# SPI_Stuff.net
KiCad netlist of a schematic drawn in Altium Designer
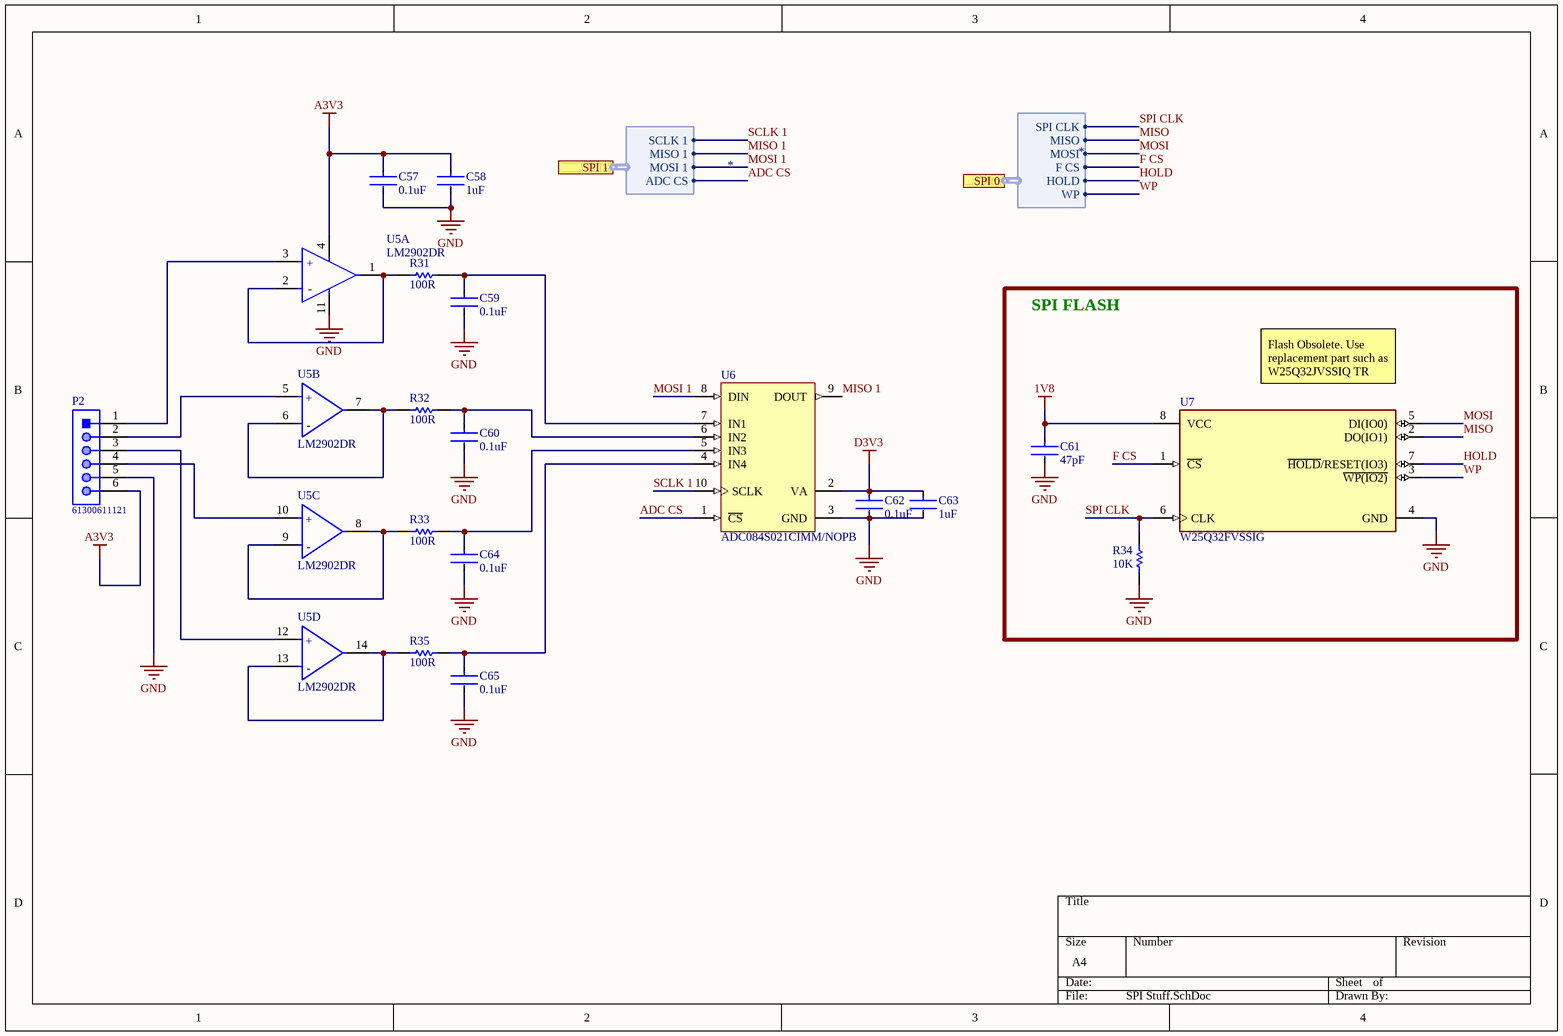
[diagram p0: SPI Stuff.SchDoc]

(export (version "E")
  (design (tool "Eeschema 10.0.6"))
  (components
    (comp (ref "C57")
      (value "0.1uF")
      (footprint "FP-GRM15-MFG")
      (description "CAP CER 0.1UF 16V X7R 0402")
      (fields (field (name "MANUFACTURER PART NUMBER") "GRM155R71C104KA88D") (field (name "TOLERANCE") "10%"))
      (libsource (lib "Altium Content Vault") (part "236180d848d6139a670b325ea6854c9"))
    )
    (comp (ref "C58")
      (value "1uF")
      (footprint "FP-GRM15-MFG")
      (description "CAP CER 0.1UF 16V X7R 0402")
      (fields (field (name "MANUFACTURER PART NUMBER") "GRM155R71C104KA88D") (field (name "TOLERANCE") "10%"))
      (libsource (lib "Altium Content Vault") (part "236180d848d6139a670b325ea6854c9"))
    )
    (comp (ref "C59")
      (value "0.1uF")
      (footprint "FP-GRM15-MFG")
      (description "CAP CER 0.1UF 16V X7R 0402")
      (fields (field (name "MANUFACTURER PART NUMBER") "GRM155R71C104KA88D") (field (name "TOLERANCE") "10%"))
      (libsource (lib "Altium Content Vault") (part "236180d848d6139a670b325ea6854c9"))
    )
    (comp (ref "C60")
      (value "0.1uF")
      (footprint "FP-GRM15-MFG")
      (description "CAP CER 0.1UF 16V X7R 0402")
      (fields (field (name "MANUFACTURER PART NUMBER") "GRM155R71C104KA88D") (field (name "TOLERANCE") "10%"))
      (libsource (lib "Altium Content Vault") (part "236180d848d6139a670b325ea6854c9"))
    )
    (comp (ref "C61")
      (value "47pF")
      (footprint "FP-GRM15-MFG")
      (description "CAP CER 0.1UF 16V X7R 0402")
      (fields (field (name "MANUFACTURER PART NUMBER") "GRM155R71C104KA88D") (field (name "TOLERANCE") "10%"))
      (libsource (lib "Altium Content Vault") (part "236180d848d6139a670b325ea6854c9"))
    )
    (comp (ref "C62")
      (value "0.1uF")
      (footprint "FP-GRM15-MFG")
      (description "CAP CER 0.1UF 16V X7R 0402")
      (fields (field (name "MANUFACTURER PART NUMBER") "GRM155R71C104KA88D") (field (name "TOLERANCE") "10%"))
      (libsource (lib "Altium Content Vault") (part "236180d848d6139a670b325ea6854c9"))
    )
    (comp (ref "C63")
      (value "1uF")
      (footprint "FP-GRM15-MFG")
      (description "CAP CER 0.1UF 16V X7R 0402")
      (fields (field (name "MANUFACTURER PART NUMBER") "GRM155R71C104KA88D") (field (name "TOLERANCE") "10%"))
      (libsource (lib "Altium Content Vault") (part "236180d848d6139a670b325ea6854c9"))
    )
    (comp (ref "C64")
      (value "0.1uF")
      (footprint "FP-GRM15-MFG")
      (description "CAP CER 0.1UF 16V X7R 0402")
      (fields (field (name "MANUFACTURER PART NUMBER") "GRM155R71C104KA88D") (field (name "TOLERANCE") "10%"))
      (libsource (lib "Altium Content Vault") (part "236180d848d6139a670b325ea6854c9"))
    )
    (comp (ref "C65")
      (value "0.1uF")
      (footprint "FP-GRM15-MFG")
      (description "CAP CER 0.1UF 16V X7R 0402")
      (fields (field (name "MANUFACTURER PART NUMBER") "GRM155R71C104KA88D") (field (name "TOLERANCE") "10%"))
      (libsource (lib "Altium Content Vault") (part "236180d848d6139a670b325ea6854c9"))
    )
    (comp (ref "P2")
      (value "61300611121")
      (footprint "61300611121")
      (description "THT Vertical Pin Header WR-PHD, Pitch 2.54 mm, Single Row, 6 pins")
      (fields (field (name "MANUFACTURER") "Wurth Elektronik") (field (name "PUBLISHER") "WurthElektronik"))
      (libsource (lib "Altium Content Vault") (part "WE-CN-1P-M-R6"))
    )
    (comp (ref "R31")
      (value "100R")
      (footprint "RESC1005X40X25LL05T05")
      (description "Chip Resistor, 0 Ohm, 0.1 W, -55 to 155 degC, 0402 (1005 Metric), RoHS, Tape and Reel")
      (fields (field (name "MANUFACTURER") "Panasonic") (field (name "TOLERANCE") "5%"))
      (libsource (lib "Altium Content Vault") (part "RES-2"))
    )
    (comp (ref "R32")
      (value "100R")
      (footprint "RESC1005X40X25LL05T05")
      (description "Chip Resistor, 0 Ohm, 0.1 W, -55 to 155 degC, 0402 (1005 Metric), RoHS, Tape and Reel")
      (fields (field (name "MANUFACTURER") "Panasonic") (field (name "TOLERANCE") "5%"))
      (libsource (lib "Altium Content Vault") (part "RES-2"))
    )
    (comp (ref "R33")
      (value "100R")
      (footprint "RESC1005X40X25LL05T05")
      (description "Chip Resistor, 0 Ohm, 0.1 W, -55 to 155 degC, 0402 (1005 Metric), RoHS, Tape and Reel")
      (fields (field (name "MANUFACTURER") "Panasonic") (field (name "TOLERANCE") "5%"))
      (libsource (lib "Altium Content Vault") (part "RES-2"))
    )
    (comp (ref "R34")
      (value "10K")
      (footprint "RESC1005X40X25LL05T05")
      (description "Chip Resistor, 0 Ohm, 0.1 W, -55 to 155 degC, 0402 (1005 Metric), RoHS, Tape and Reel")
      (fields (field (name "MANUFACTURER") "Panasonic") (field (name "TOLERANCE") "5%"))
      (libsource (lib "Altium Content Vault") (part "RES-2"))
    )
    (comp (ref "R35")
      (value "100R")
      (footprint "RESC1005X40X25LL05T05")
      (description "Chip Resistor, 0 Ohm, 0.1 W, -55 to 155 degC, 0402 (1005 Metric), RoHS, Tape and Reel")
      (fields (field (name "MANUFACTURER") "Panasonic") (field (name "TOLERANCE") "5%"))
      (libsource (lib "Altium Content Vault") (part "RES-2"))
    )
    (comp (ref "U5")
      (value "LM2902DR")
      (footprint "FP-D0014A-IPC_A")
      (description "IC OPAMP GP 4 CIRCUIT 14SOIC")
      (libsource (lib "Altium Content Vault") (part "b02d0cb41c0d90ddc6f34c0e90b5c12"))
    )
    (comp (ref "U6")
      (value "ADC084S021CIMM/NOPB")
      (footprint "MUB10A_N")
      (description "4 Channel, 50 kSPS to 200 kSPS, 8-Bit A/D Converter, 10-pin Mini SOIC, Pb-Free")
      (fields (field (name "MANUFACTURER") "National Semiconductor"))
      (libsource (lib "Altium Content Vault") (part "CON-ADC-ADC104S101CIMM"))
    )
    (comp (ref "U7")
      (value "W25Q32FVSSIG")
      (footprint "FP-SS-MFG")
      (description "IC FLASH 32M SPI 104MHZ 8SOIC")
      (fields
        (field (name "MANUFACTURER") "Winbond")
        (field (name "OCTOPART") "https://octopart.com/w25q32fvssig-winbond-23896462")
      )
      (libsource (lib "Altium Content Vault") (part "4804fbe011262506d6ec6a9051036b0"))
    )
  )
  (nets
    (net (code "2") (name "/ADC CS") (class "Default")
      (node (ref "U6") (pin "1") (pinfunction "~{CS}_1") (pintype "input"))
    )
    (net (code "3") (name "/F CS") (class "Default")
      (node (ref "U7") (pin "1") (pinfunction "~{CS}_1") (pintype "input"))
    )
    (net (code "4") (name "/HOLD") (class "Default")
      (node (ref "U7") (pin "7") (pinfunction "~{HOLD}/RESET(IO3)_7") (pintype "bidirectional"))
    )
    (net (code "5") (name "/MISO") (class "Default")
      (node (ref "U7") (pin "2") (pinfunction "DO(IO1)_2") (pintype "bidirectional"))
    )
    (net (code "6") (name "/MISO 1") (class "Default")
      (node (ref "U6") (pin "9") (pinfunction "DOUT_9") (pintype "output"))
    )
    (net (code "7") (name "/MOSI") (class "Default")
      (node (ref "U7") (pin "5") (pinfunction "DI(IO0)_5") (pintype "bidirectional"))
    )
    (net (code "8") (name "/MOSI 1") (class "Default")
      (node (ref "U6") (pin "8") (pinfunction "DIN_8") (pintype "input"))
    )
    (net (code "9") (name "/SCLK 1") (class "Default")
      (node (ref "U6") (pin "10") (pinfunction "SCLK_10") (pintype "input"))
    )
    (net (code "10") (name "/SPI CLK") (class "Default")
      (node (ref "R34") (pin "2") (pinfunction "2_2") (pintype "passive"))
      (node (ref "U7") (pin "6") (pinfunction "CLK_6") (pintype "input"))
    )
    (net (code "11") (name "/WP") (class "Default")
      (node (ref "U7") (pin "3") (pinfunction "~{WP(IO2)}_3") (pintype "bidirectional"))
    )
    (net (code "13") (name "1V8") (class "Default")
      (node (ref "C61") (pin "2") (pinfunction "2_2") (pintype "passive"))
      (node (ref "U7") (pin "8") (pinfunction "VCC_8") (pintype "power_in"))
    )
    (net (code "14") (name "A3V3") (class "Default")
      (node (ref "C57") (pin "2") (pinfunction "2_2") (pintype "passive"))
      (node (ref "C58") (pin "2") (pinfunction "2_2") (pintype "passive"))
      (node (ref "P2") (pin "6") (pinfunction "6_6") (pintype "passive"))
      (node (ref "U5") (pin "4") (pinfunction "VCC_4") (pintype "power_in"))
    )
    (net (code "15") (name "D3V3") (class "Default")
      (node (ref "C62") (pin "2") (pinfunction "2_2") (pintype "passive"))
      (node (ref "C63") (pin "2") (pinfunction "2_2") (pintype "passive"))
      (node (ref "U6") (pin "2") (pinfunction "VA_2") (pintype "power_in"))
    )
    (net (code "16") (name "GND") (class "Default")
      (node (ref "C57") (pin "1") (pinfunction "1_1") (pintype "passive"))
      (node (ref "C58") (pin "1") (pinfunction "1_1") (pintype "passive"))
      (node (ref "C59") (pin "1") (pinfunction "1_1") (pintype "passive"))
      (node (ref "C60") (pin "1") (pinfunction "1_1") (pintype "passive"))
      (node (ref "C61") (pin "1") (pinfunction "1_1") (pintype "passive"))
      (node (ref "C62") (pin "1") (pinfunction "1_1") (pintype "passive"))
      (node (ref "C63") (pin "1") (pinfunction "1_1") (pintype "passive"))
      (node (ref "C64") (pin "1") (pinfunction "1_1") (pintype "passive"))
      (node (ref "C65") (pin "1") (pinfunction "1_1") (pintype "passive"))
      (node (ref "P2") (pin "5") (pinfunction "5_5") (pintype "passive"))
      (node (ref "R34") (pin "1") (pinfunction "1_1") (pintype "passive"))
      (node (ref "U5") (pin "11") (pinfunction "GND_11") (pintype "power_in"))
      (node (ref "U6") (pin "3") (pinfunction "GND_3") (pintype "power_in"))
      (node (ref "U7") (pin "4") (pinfunction "GND_4") (pintype "power_in"))
    )
    (net (code "17") (name "Net-(U5A-1IN+)") (class "Default")
      (node (ref "P2") (pin "1") (pinfunction "1_1") (pintype "passive"))
      (node (ref "U5") (pin "3") (pinfunction "1IN+_3") (pintype "tri_state"))
    )
    (net (code "18") (name "Net-(U5A-1IN-)") (class "Default")
      (node (ref "R31") (pin "2") (pinfunction "2_2") (pintype "passive"))
      (node (ref "U5") (pin "1") (pinfunction "1OUT_1") (pintype "passive"))
      (node (ref "U5") (pin "2") (pinfunction "1IN-_2") (pintype "tri_state"))
    )
    (net (code "19") (name "Net-(U5B-2IN+)") (class "Default")
      (node (ref "P2") (pin "2") (pinfunction "2_2") (pintype "passive"))
      (node (ref "U5") (pin "5") (pinfunction "2IN+_5") (pintype "tri_state"))
    )
    (net (code "20") (name "Net-(U5B-2IN-)") (class "Default")
      (node (ref "R32") (pin "2") (pinfunction "2_2") (pintype "passive"))
      (node (ref "U5") (pin "6") (pinfunction "2IN-_6") (pintype "tri_state"))
      (node (ref "U5") (pin "7") (pinfunction "2OUT_7") (pintype "passive"))
    )
    (net (code "21") (name "Net-(U5C-3IN+)") (class "Default")
      (node (ref "P2") (pin "4") (pinfunction "4_4") (pintype "passive"))
      (node (ref "U5") (pin "10") (pinfunction "3IN+_10") (pintype "tri_state"))
    )
    (net (code "22") (name "Net-(U5C-3IN-)") (class "Default")
      (node (ref "R33") (pin "2") (pinfunction "2_2") (pintype "passive"))
      (node (ref "U5") (pin "8") (pinfunction "3OUT_8") (pintype "passive"))
      (node (ref "U5") (pin "9") (pinfunction "3IN-_9") (pintype "tri_state"))
    )
    (net (code "23") (name "Net-(U5D-4IN+)") (class "Default")
      (node (ref "P2") (pin "3") (pinfunction "3_3") (pintype "passive"))
      (node (ref "U5") (pin "12") (pinfunction "4IN+_12") (pintype "tri_state"))
    )
    (net (code "24") (name "Net-(U5D-4IN-)") (class "Default")
      (node (ref "R35") (pin "2") (pinfunction "2_2") (pintype "passive"))
      (node (ref "U5") (pin "13") (pinfunction "4IN-_13") (pintype "tri_state"))
      (node (ref "U5") (pin "14") (pinfunction "4OUT_14") (pintype "passive"))
    )
    (net (code "25") (name "Net-(U6-IN1)") (class "Default")
      (node (ref "C59") (pin "2") (pinfunction "2_2") (pintype "passive"))
      (node (ref "R31") (pin "1") (pinfunction "1_1") (pintype "passive"))
      (node (ref "U6") (pin "7") (pinfunction "IN1_7") (pintype "input"))
    )
    (net (code "26") (name "Net-(U6-IN2)") (class "Default")
      (node (ref "C60") (pin "2") (pinfunction "2_2") (pintype "passive"))
      (node (ref "R32") (pin "1") (pinfunction "1_1") (pintype "passive"))
      (node (ref "U6") (pin "6") (pinfunction "IN2_6") (pintype "input"))
    )
    (net (code "27") (name "Net-(U6-IN3)") (class "Default")
      (node (ref "C64") (pin "2") (pinfunction "2_2") (pintype "passive"))
      (node (ref "R33") (pin "1") (pinfunction "1_1") (pintype "passive"))
      (node (ref "U6") (pin "5") (pinfunction "IN3_5") (pintype "input"))
    )
    (net (code "28") (name "Net-(U6-IN4)") (class "Default")
      (node (ref "C65") (pin "2") (pinfunction "2_2") (pintype "passive"))
      (node (ref "R35") (pin "1") (pinfunction "1_1") (pintype "passive"))
      (node (ref "U6") (pin "4") (pinfunction "IN4_4") (pintype "input"))
    )
  )
)
